# MicroController.net
KiCad netlist of a schematic drawn in Altium Designer
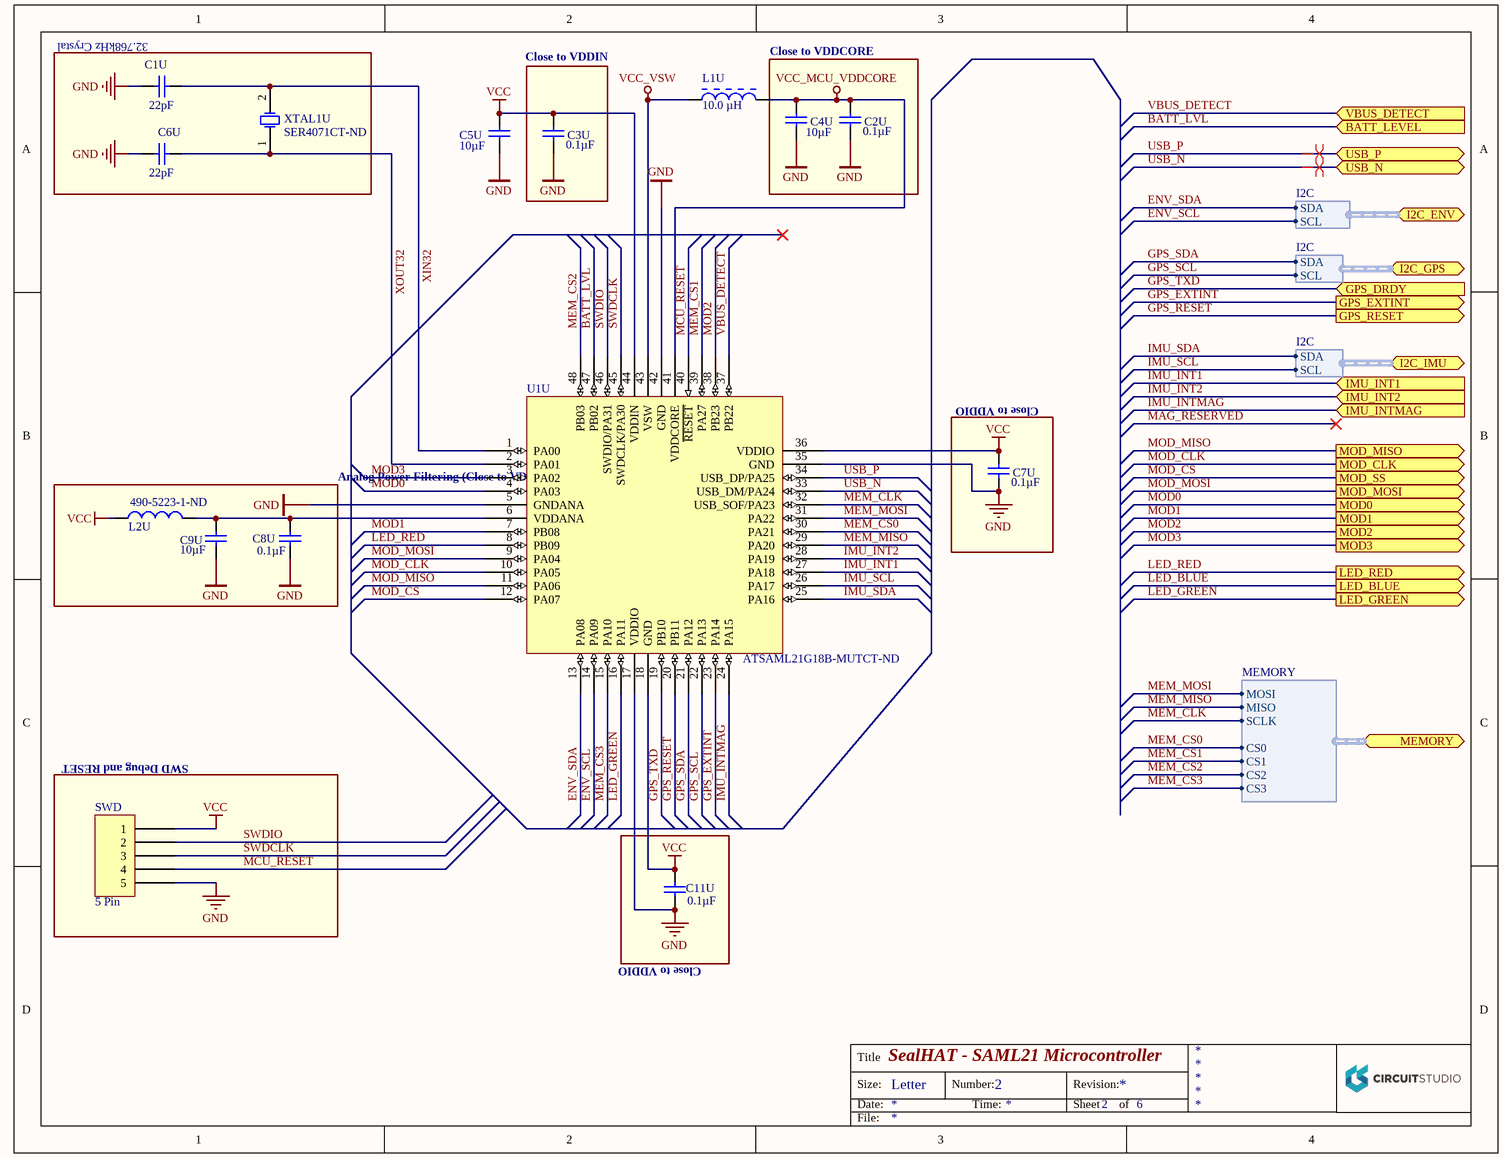
[diagram p0: MicroController.SchDoc]

(export (version "E")
  (design (tool "Eeschema 10.0.6"))
  (components
    (comp (ref "C1U")
      (value "GRM1555C1H220FA01D")
      (footprint "C0402M")
      (description "CAP CER 22PF 50V C0G/NP0 0402")
      (fields
        (field (name "HOUSEPART") "NO")
        (field (name "TOLERANCE") "±1%")
        (field (name "CAPACITANCE") "22pF")
      )
      (libsource (lib "MF_Passives") (part "CAPACITOR_NP"))
    )
    (comp (ref "C2U")
      (value "GCM188R71C104KA37D")
      (footprint "C0603N")
      (fields
        (field (name "HOUSEPART") "NO")
        (field (name "TOLERANCE") "±10%")
        (field (name "VOLTAGE") "16V")
        (field (name "CAPACITANCE") "0.1µF")
      )
      (libsource (lib "MF_Passives") (part "CAPACITOR_NP"))
    )
    (comp (ref "C3U")
      (value "GCM188R71C104KA37D")
      (footprint "C0603N")
      (fields
        (field (name "HOUSEPART") "NO")
        (field (name "TOLERANCE") "±10%")
        (field (name "VOLTAGE") "16V")
        (field (name "CAPACITANCE") "0.1µF")
      )
      (libsource (lib "MF_Passives") (part "CAPACITOR_NP"))
    )
    (comp (ref "C4U")
      (value "GRT188R61C106KE13D")
      (footprint "C0603N")
      (description "10µF 16V Ceramic Capacitor X5R 0603")
      (fields
        (field (name "HOUSEPART") "NO")
        (field (name "TOLERANCE") "±10%")
        (field (name "CAPACITANCE") "10µF")
      )
      (libsource (lib "MF_Passives") (part "CAPACITOR_NP"))
    )
    (comp (ref "C5U")
      (value "GRT188R61C106KE13D")
      (footprint "C0603N")
      (description "10µF 16V Ceramic Capacitor X5R 0603")
      (fields
        (field (name "HOUSEPART") "NO")
        (field (name "TOLERANCE") "±10%")
        (field (name "CAPACITANCE") "10µF")
      )
      (libsource (lib "MF_Passives") (part "CAPACITOR_NP"))
    )
    (comp (ref "C6U")
      (value "GRM1555C1H220FA01D")
      (footprint "C0402M")
      (description "CAP CER 22PF 50V C0G/NP0 0402")
      (fields
        (field (name "HOUSEPART") "NO")
        (field (name "TOLERANCE") "±1%")
        (field (name "CAPACITANCE") "22pF")
      )
      (libsource (lib "MF_Passives") (part "CAPACITOR_NP"))
    )
    (comp (ref "C7U")
      (value "GCM188R71C104KA37D")
      (footprint "C0603N")
      (fields
        (field (name "HOUSEPART") "NO")
        (field (name "TOLERANCE") "±10%")
        (field (name "VOLTAGE") "16V")
        (field (name "CAPACITANCE") "0.1µF")
      )
      (libsource (lib "MF_Passives") (part "CAPACITOR_NP"))
    )
    (comp (ref "C8U")
      (value "GCM188R71C104KA37D")
      (footprint "C0603N")
      (fields
        (field (name "HOUSEPART") "NO")
        (field (name "TOLERANCE") "±10%")
        (field (name "VOLTAGE") "16V")
        (field (name "CAPACITANCE") "0.1µF")
      )
      (libsource (lib "MF_Passives") (part "CAPACITOR_NP"))
    )
    (comp (ref "C9U")
      (value "GRT188R61C106KE13D")
      (footprint "C0603N")
      (description "10µF 16V Ceramic Capacitor X5R 0603")
      (fields
        (field (name "HOUSEPART") "NO")
        (field (name "TOLERANCE") "±10%")
        (field (name "CAPACITANCE") "10µF")
      )
      (libsource (lib "MF_Passives") (part "CAPACITOR_NP"))
    )
    (comp (ref "C11U")
      (value "GCM188R71C104KA37D")
      (footprint "C0603N")
      (fields
        (field (name "HOUSEPART") "NO")
        (field (name "TOLERANCE") "±10%")
        (field (name "VOLTAGE") "16V")
        (field (name "CAPACITANCE") "0.1µF")
      )
      (libsource (lib "MF_Passives") (part "CAPACITOR_NP"))
    )
    (comp (ref "L1U")
      (value "SRN3015-100M")
      (footprint "SRN3015")
      (fields (field (name "INDUCTANCE") "10.0 µH"))
      (libsource (lib "Bourns") (part "CMP-911278-2"))
    )
    (comp (ref "L2U")
      (value "BLM18PG471SN1D")
      (footprint "R0603N")
      (description "FERRITE BEAD 470 OHM 0603 1LN")
      (fields
        (field (name "HOUSEPART") "NO")
        (field (name "MPN") "LI0603G221R-10")
        (field (name "SUPPLIER PART NUMBER 1") "490-5223-1-ND")
      )
      (libsource (lib "MF_Passives") (part "INDUCTOR"))
    )
    (comp (ref "SWD")
      (value "5 Pin")
      (footprint "Pinhead254_90_1x5")
      (libsource (lib "Connectors") (part "5 Pin"))
    )
    (comp (ref "U1U")
      (value "ATSAML21G18B-MUT")
      (footprint "TQFP48_7X7_P50")
      (fields (field (name "SUPPLIER PART NUMBER 1") "ATSAML21G18B-MUTCT-ND"))
      (libsource (lib "Microchip") (part "ATSAML21G18B-MUT"))
    )
    (comp (ref "XTAL1U")
      (value "FC-135 32.7680KA-A3")
      (footprint "FC-135R$2F$FC-135")
      (description "FC-135 Series 32.768 KHz ±20 ppm 12.5 pF -40 to +85°C Surface Mount Crystal")
      (fields (field (name "MANUFACTURER") "epson") (field (name "SUPPLIER PART NUMBER 1") "SER4071CT-ND"))
      (libsource (lib "FC-135R_RC-135") (part "FC-13532.7680KA-A3"))
    )
  )
  (nets
    (net (code "3") (name "/BATT_LVL") (class "Default")
      (node (ref "U1U") (pin "47") (pinfunction "PB02_47") (pintype "bidirectional"))
    )
    (net (code "4") (name "/ENV_SCL") (class "Default")
      (node (ref "U1U") (pin "14") (pinfunction "PA09_14") (pintype "bidirectional"))
    )
    (net (code "5") (name "/ENV_SDA") (class "Default")
      (node (ref "U1U") (pin "13") (pinfunction "PA08_13") (pintype "bidirectional"))
    )
    (net (code "6") (name "/GPS_EXTINT") (class "Default")
      (node (ref "U1U") (pin "23") (pinfunction "PA14_23") (pintype "bidirectional"))
    )
    (net (code "7") (name "/GPS_RESET") (class "Default")
      (node (ref "U1U") (pin "20") (pinfunction "PB11_20") (pintype "bidirectional"))
    )
    (net (code "8") (name "/GPS_SCL") (class "Default")
      (node (ref "U1U") (pin "22") (pinfunction "PA13_22") (pintype "bidirectional"))
    )
    (net (code "9") (name "/GPS_SDA") (class "Default")
      (node (ref "U1U") (pin "21") (pinfunction "PA12_21") (pintype "bidirectional"))
    )
    (net (code "10") (name "/GPS_TXD") (class "Default")
      (node (ref "U1U") (pin "19") (pinfunction "PB10_19") (pintype "bidirectional"))
    )
    (net (code "11") (name "/IMU_INT1") (class "Default")
      (node (ref "U1U") (pin "27") (pinfunction "PA18_27") (pintype "bidirectional"))
    )
    (net (code "12") (name "/IMU_INT2") (class "Default")
      (node (ref "U1U") (pin "28") (pinfunction "PA19_28") (pintype "bidirectional"))
    )
    (net (code "13") (name "/IMU_INTMAG") (class "Default")
      (node (ref "U1U") (pin "24") (pinfunction "PA15_24") (pintype "bidirectional"))
    )
    (net (code "14") (name "/IMU_SCL") (class "Default")
      (node (ref "U1U") (pin "26") (pinfunction "PA17_26") (pintype "bidirectional"))
    )
    (net (code "15") (name "/IMU_SDA") (class "Default")
      (node (ref "U1U") (pin "25") (pinfunction "PA16_25") (pintype "bidirectional"))
    )
    (net (code "17") (name "/LED_GREEN") (class "Default")
      (node (ref "U1U") (pin "16") (pinfunction "PA11_16") (pintype "bidirectional"))
    )
    (net (code "18") (name "/LED_RED") (class "Default")
      (node (ref "U1U") (pin "8") (pinfunction "PB09_8") (pintype "bidirectional"))
    )
    (net (code "20") (name "/MCU_RESET") (class "Default")
      (node (ref "SWD") (pin "4") (pinfunction "4_4") (pintype "passive"))
      (node (ref "U1U") (pin "40") (pinfunction "~{RESET}_40") (pintype "input"))
    )
    (net (code "21") (name "/MEM_CLK") (class "Default")
      (node (ref "U1U") (pin "32") (pinfunction "USB_SOF/PA23_32") (pintype "bidirectional"))
    )
    (net (code "22") (name "/MEM_CS0") (class "Default")
      (node (ref "U1U") (pin "30") (pinfunction "PA21_30") (pintype "bidirectional"))
    )
    (net (code "23") (name "/MEM_CS1") (class "Default")
      (node (ref "U1U") (pin "39") (pinfunction "PA27_39") (pintype "bidirectional"))
    )
    (net (code "24") (name "/MEM_CS2") (class "Default")
      (node (ref "U1U") (pin "48") (pinfunction "PB03_48") (pintype "bidirectional"))
    )
    (net (code "25") (name "/MEM_CS3") (class "Default")
      (node (ref "U1U") (pin "15") (pinfunction "PA10_15") (pintype "bidirectional"))
    )
    (net (code "26") (name "/MEM_MISO") (class "Default")
      (node (ref "U1U") (pin "29") (pinfunction "PA20_29") (pintype "bidirectional"))
    )
    (net (code "27") (name "/MEM_MOSI") (class "Default")
      (node (ref "U1U") (pin "31") (pinfunction "PA22_31") (pintype "bidirectional"))
    )
    (net (code "28") (name "/MOD0") (class "Default")
      (node (ref "U1U") (pin "4") (pinfunction "PA03_4") (pintype "bidirectional"))
    )
    (net (code "29") (name "/MOD1") (class "Default")
      (node (ref "U1U") (pin "7") (pinfunction "PB08_7") (pintype "bidirectional"))
    )
    (net (code "30") (name "/MOD2") (class "Default")
      (node (ref "U1U") (pin "38") (pinfunction "PB23_38") (pintype "bidirectional"))
    )
    (net (code "31") (name "/MOD3") (class "Default")
      (node (ref "U1U") (pin "3") (pinfunction "PA02_3") (pintype "bidirectional"))
    )
    (net (code "32") (name "/MOD_CLK") (class "Default")
      (node (ref "U1U") (pin "10") (pinfunction "PA05_10") (pintype "bidirectional"))
    )
    (net (code "33") (name "/MOD_CS") (class "Default")
      (node (ref "U1U") (pin "12") (pinfunction "PA07_12") (pintype "bidirectional"))
    )
    (net (code "34") (name "/MOD_MISO") (class "Default")
      (node (ref "U1U") (pin "11") (pinfunction "PA06_11") (pintype "bidirectional"))
    )
    (net (code "35") (name "/MOD_MOSI") (class "Default")
      (node (ref "U1U") (pin "9") (pinfunction "PA04_9") (pintype "bidirectional"))
    )
    (net (code "36") (name "/SWDCLK") (class "Default")
      (node (ref "SWD") (pin "3") (pinfunction "3_3") (pintype "passive"))
      (node (ref "U1U") (pin "45") (pinfunction "SWDCLK/PA30_45") (pintype "bidirectional"))
    )
    (net (code "37") (name "/SWDIO") (class "Default")
      (node (ref "SWD") (pin "2") (pinfunction "2_2") (pintype "passive"))
      (node (ref "U1U") (pin "46") (pinfunction "SWDIO/PA31_46") (pintype "bidirectional"))
    )
    (net (code "38") (name "/USB_N") (class "Default")
      (node (ref "U1U") (pin "33") (pinfunction "USB_DM/PA24_33") (pintype "bidirectional"))
    )
    (net (code "39") (name "/USB_P") (class "Default")
      (node (ref "U1U") (pin "34") (pinfunction "USB_DP/PA25_34") (pintype "bidirectional"))
    )
    (net (code "40") (name "/VBUS_DETECT") (class "Default")
      (node (ref "U1U") (pin "37") (pinfunction "PB22_37") (pintype "bidirectional"))
    )
    (net (code "41") (name "/XIN32") (class "Default")
      (node (ref "C1U") (pin "1") (pinfunction "1_1") (pintype "passive"))
      (node (ref "U1U") (pin "1") (pinfunction "PA00_1") (pintype "bidirectional"))
      (node (ref "XTAL1U") (pin "2") (pinfunction "X2_2") (pintype "passive"))
    )
    (net (code "42") (name "/XOUT32") (class "Default")
      (node (ref "C6U") (pin "1") (pinfunction "1_1") (pintype "passive"))
      (node (ref "U1U") (pin "2") (pinfunction "PA01_2") (pintype "bidirectional"))
      (node (ref "XTAL1U") (pin "1") (pinfunction "X1_1") (pintype "passive"))
    )
    (net (code "45") (name "GND") (class "Default")
      (node (ref "C11U") (pin "2") (pinfunction "2_2") (pintype "passive"))
      (node (ref "C1U") (pin "2") (pinfunction "2_2") (pintype "passive"))
      (node (ref "C2U") (pin "1") (pinfunction "1_1") (pintype "passive"))
      (node (ref "C3U") (pin "1") (pinfunction "1_1") (pintype "passive"))
      (node (ref "C4U") (pin "1") (pinfunction "1_1") (pintype "passive"))
      (node (ref "C5U") (pin "1") (pinfunction "1_1") (pintype "passive"))
      (node (ref "C6U") (pin "2") (pinfunction "2_2") (pintype "passive"))
      (node (ref "C7U") (pin "1") (pinfunction "1_1") (pintype "passive"))
      (node (ref "C8U") (pin "2") (pinfunction "2_2") (pintype "passive"))
      (node (ref "C9U") (pin "1") (pinfunction "1_1") (pintype "passive"))
      (node (ref "SWD") (pin "5") (pinfunction "5_5") (pintype "passive"))
      (node (ref "U1U") (pin "17") (pinfunction "VDDIO_17") (pintype "power_in"))
      (node (ref "U1U") (pin "35") (pinfunction "GND_35") (pintype "passive"))
      (node (ref "U1U") (pin "42") (pinfunction "GND_42") (pintype "passive"))
      (node (ref "U1U") (pin "5") (pinfunction "GNDANA_5") (pintype "passive"))
    )
    (net (code "46") (name "Net-(U1U-VDDANA)") (class "Default")
      (node (ref "C8U") (pin "1") (pinfunction "1_1") (pintype "passive"))
      (node (ref "C9U") (pin "2") (pinfunction "2_2") (pintype "passive"))
      (node (ref "L2U") (pin "2") (pinfunction "2_2") (pintype "passive"))
      (node (ref "U1U") (pin "6") (pinfunction "VDDANA_6") (pintype "power_in"))
    )
    (net (code "47") (name "VCC") (class "Default")
      (node (ref "C11U") (pin "1") (pinfunction "1_1") (pintype "passive"))
      (node (ref "C3U") (pin "2") (pinfunction "2_2") (pintype "passive"))
      (node (ref "C5U") (pin "2") (pinfunction "2_2") (pintype "passive"))
      (node (ref "C7U") (pin "2") (pinfunction "2_2") (pintype "passive"))
      (node (ref "L2U") (pin "1") (pinfunction "1_1") (pintype "passive"))
      (node (ref "SWD") (pin "1") (pinfunction "1_1") (pintype "passive"))
      (node (ref "U1U") (pin "18") (pinfunction "GND_18") (pintype "passive"))
      (node (ref "U1U") (pin "36") (pinfunction "VDDIO_36") (pintype "power_in"))
      (node (ref "U1U") (pin "44") (pinfunction "VDDIN_44") (pintype "power_in"))
    )
    (net (code "48") (name "VCC_MCU_VDDCORE") (class "Default")
      (node (ref "C2U") (pin "2") (pinfunction "2_2") (pintype "passive"))
      (node (ref "C4U") (pin "2") (pinfunction "2_2") (pintype "passive"))
      (node (ref "L1U") (pin "2") (pinfunction "2_2") (pintype "passive"))
      (node (ref "U1U") (pin "41") (pinfunction "VDDCORE_41") (pintype "power_in"))
    )
    (net (code "49") (name "VCC_VSW") (class "Default")
      (node (ref "L1U") (pin "1") (pinfunction "1_1") (pintype "passive"))
      (node (ref "U1U") (pin "43") (pinfunction "VSW_43") (pintype "power_in"))
    )
  )
)
